# Current_Sense.net
KiCad netlist of a schematic drawn in Altium Designer
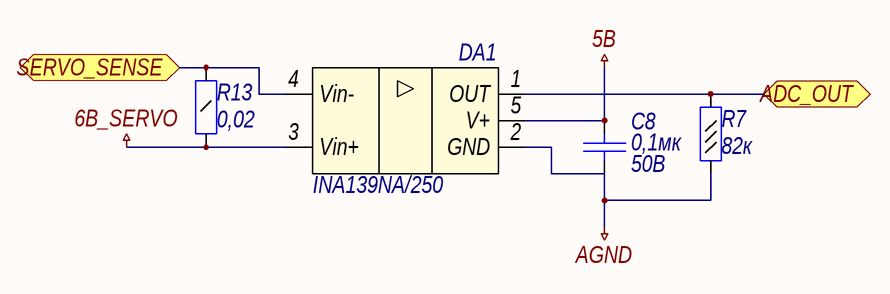
[diagram p0: Current_Sense.SchDoc]

(export (version "E")
  (design (tool "Eeschema 10.0.6"))
  (components
    (comp (ref "C8")
      (value "0,1мк")
      (footprint "C0603")
      (description "Конденсатор")
      (fields (field (name "VOLTAGE") "50B") (field (name "PART NUMBER") "GRM188R71H104KA93D"))
      (libsource (lib "MOP44") (part "Capacitor"))
    )
    (comp (ref "DA1")
      (value "INA139NA/250")
      (footprint "SOT23-5")
      (description "Измерительный датчик тока")
      (libsource (lib "MOP44") (part "INA1x9"))
    )
    (comp (ref "R7")
      (value "82к")
      (footprint "R0603")
      (description "Резистор")
      (fields (field (name "PART NUMBER") "RC0603FR-0782KL") (field (name "POWER") "0,062Вт"))
      (libsource (lib "MOP44") (part "Resistor_0,062Вт"))
    )
    (comp (ref "R13")
      (value "0,02")
      (footprint "R1206")
      (description "Резистор")
      (fields (field (name "PART NUMBER") "RL1206FR-070R02L") (field (name "POWER") "0,25Вт"))
      (libsource (lib "MOP44") (part "Resistor_0,25Вт"))
    )
  )
  (nets
    (net (code "1") (name "/ADC_OUT") (class "Default")
      (node (ref "DA1") (pin "1") (pinfunction "OUT_1") (pintype "power_in"))
      (node (ref "R7") (pin "2") (pinfunction "2_2") (pintype "passive"))
    )
    (net (code "2") (name "/SERVO_SENSE") (class "Default")
      (node (ref "DA1") (pin "4") (pinfunction "Vin-_4") (pintype "power_in"))
      (node (ref "R13") (pin "2") (pinfunction "2_2") (pintype "passive"))
    )
    (net (code "3") (name "5В") (class "Default")
      (node (ref "C8") (pin "2") (pinfunction "2_2") (pintype "passive"))
      (node (ref "DA1") (pin "5") (pinfunction "V+_5") (pintype "power_in"))
    )
    (net (code "4") (name "6В_SERVO") (class "Default")
      (node (ref "DA1") (pin "3") (pinfunction "Vin+_3") (pintype "power_in"))
      (node (ref "R13") (pin "1") (pinfunction "1_1") (pintype "passive"))
    )
    (net (code "5") (name "AGND") (class "Default")
      (node (ref "C8") (pin "1") (pinfunction "1_1") (pintype "passive"))
      (node (ref "DA1") (pin "2") (pinfunction "GND_2") (pintype "power_in"))
      (node (ref "R7") (pin "1") (pinfunction "1_1") (pintype "passive"))
    )
  )
)
